# RS485NFlash.net
KiCad netlist of a schematic drawn in Altium Designer
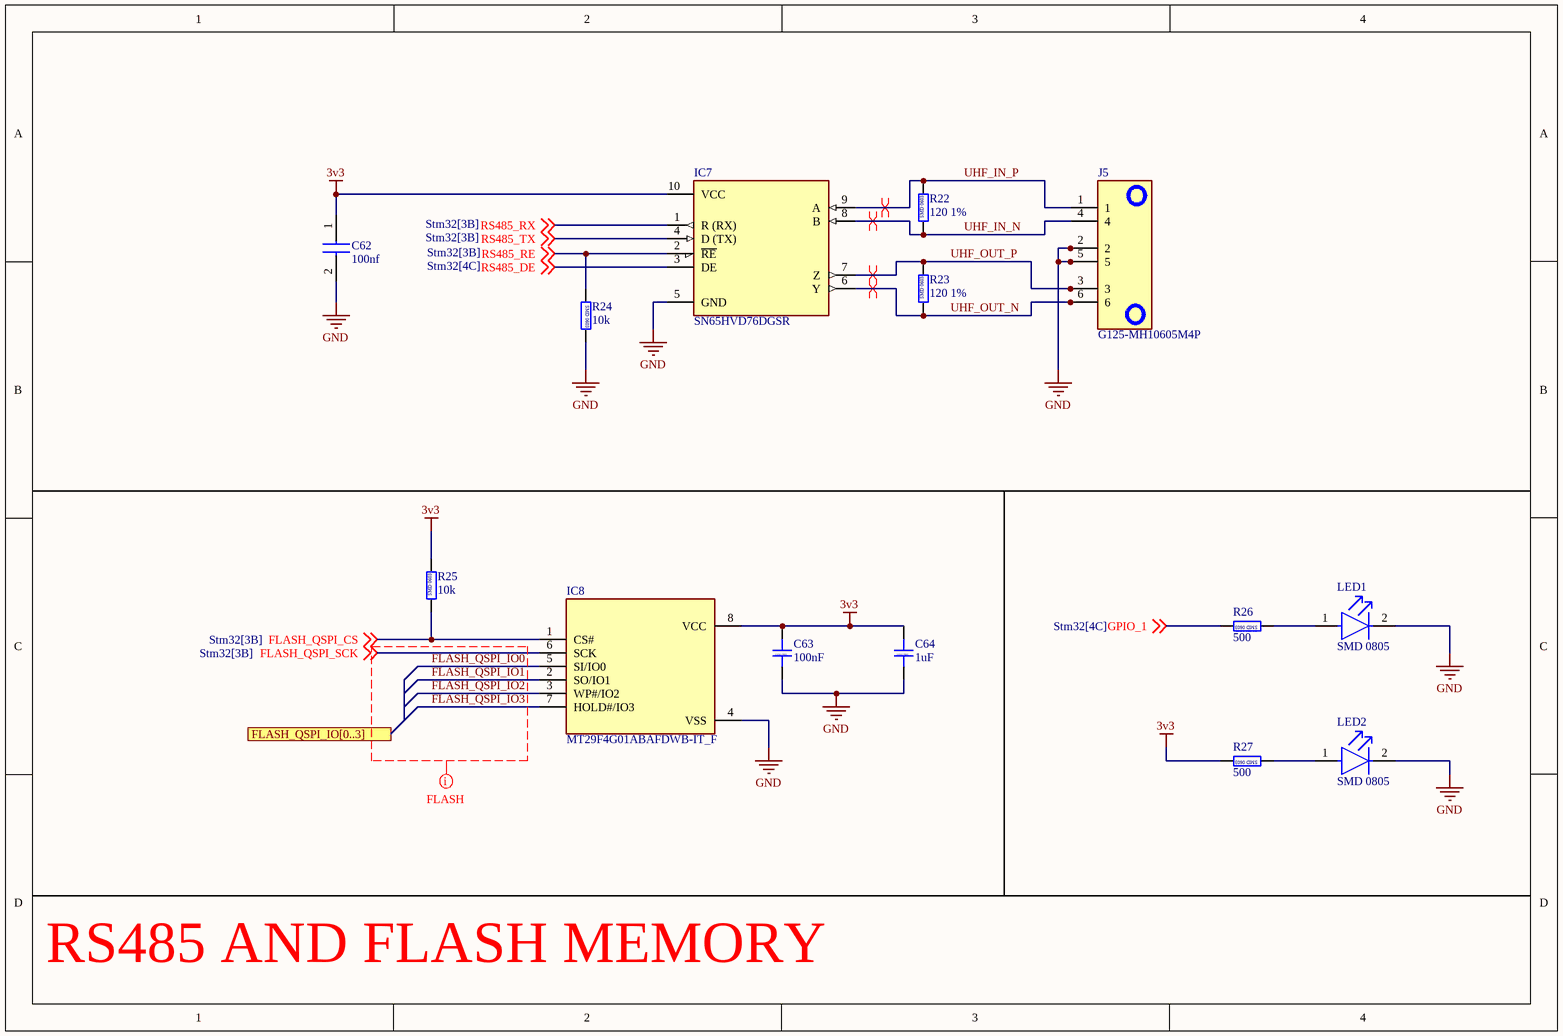
[diagram p0: RS485NFlash.SchDoc]

(export (version "E")
  (design (tool "Eeschema 10.0.6"))
  (components
    (comp (ref "C62")
      (value "100nf")
      (footprint "SamacSys:CAPC1608X87N")
      (description "Capacitor")
      (fields
        (field (name "MANUFACTURER_PART_NUMBER") "0603N470J500CT")
        (field (name "MOUSER PART NUMBER") "791-0603N470J500CT")
      )
      (libsource (lib "SamacSys") (part "0603N470J500CT"))
    )
    (comp (ref "C63")
      (value "100nF")
      (footprint "CAP_0603")
      (description "Capacitor SMD 0603 RATED")
      (libsource (lib "STeRG-Passives-Standard") (part "Capacitor-SMD-0603"))
    )
    (comp (ref "C64")
      (value "1uF")
      (footprint "CAP_0603")
      (description "Capacitor SMD 0603 RATED")
      (libsource (lib "STeRG-Passives-Standard") (part "Capacitor-SMD-0603"))
    )
    (comp (ref "IC7")
      (value "SN65HVD76DGSR")
      (footprint "SOP50P490X110-10N")
      (description "RS485 Full Duplex Transciever")
      (fields (field (name "MOUSER PART NUMBER") "595-SN65HVD76DGSR"))
      (libsource (lib "STeRG-ICs-Standard") (part "SN65HVD76DGSR"))
    )
    (comp (ref "IC8")
      (value "MT29F4G01ABAFDWB-IT_F")
      (footprint "SamacSys:SON127P800X600X65-8N")
      (description "Integrated Circuit")
      (fields
        (field (name "MANUFACTURER_PART_NUMBER") "MT29F4G01ABAFDWB-IT:F")
        (field (name "MOUSER PART NUMBER") "340-359563")
      )
      (libsource (lib "SamacSys") (part "MT29F4G01ABAFDWB-IT_F"))
    )
    (comp (ref "J5")
      (value "G125-MH10605M4P")
      (footprint "G125-MH10605M4P_1")
      (description "Connector")
      (fields (field (name "MOUSER PART NUMBER") "855-G125MH1065M4PM4P"))
      (libsource (lib "STeRG-Passives-Standard") (part "G125-MH10605M4P"))
    )
    (comp (ref "LED1")
      (value "SMD 0805")
      (footprint "FP-SM0805YCL-MFG")
      (description "LED YELLOW CLEAR 0805 SMD")
      (libsource (lib "Altium Content Vault") (part "ab1c01a81903e929fc6c44469aada92"))
    )
    (comp (ref "LED2")
      (value "SMD 0805")
      (footprint "FP-SM0805YCL-MFG")
      (description "LED YELLOW CLEAR 0805 SMD")
      (libsource (lib "Altium Content Vault") (part "ab1c01a81903e929fc6c44469aada92"))
    )
    (comp (ref "R22")
      (value "120 1%")
      (footprint "RES_0603")
      (description "Resistor SMD 0603 RATED")
      (libsource (lib "STeRG-Passives-Standard") (part "Resistor-SMD-0603"))
    )
    (comp (ref "R23")
      (value "120 1%")
      (footprint "RES_0603")
      (description "Resistor SMD 0603 RATED")
      (libsource (lib "STeRG-Passives-Standard") (part "Resistor-SMD-0603"))
    )
    (comp (ref "R24")
      (value "10k")
      (footprint "RES_0603")
      (description "Resistor SMD 0603 RATED")
      (libsource (lib "STeRG-Passives-Standard") (part "Resistor-SMD-0603"))
    )
    (comp (ref "R25")
      (value "10k")
      (footprint "RES_0603")
      (description "Resistor SMD 0603 RATED")
      (libsource (lib "STeRG-Passives-Standard") (part "Resistor-SMD-0603"))
    )
    (comp (ref "R26")
      (value "500")
      (footprint "RES_0603")
      (description "Resistor SMD 0603 RATED")
      (libsource (lib "STeRG-Passives-Standard") (part "Resistor-SMD-0603"))
    )
    (comp (ref "R27")
      (value "500")
      (footprint "RES_0603")
      (description "Resistor SMD 0603 RATED")
      (libsource (lib "STeRG-Passives-Standard") (part "Resistor-SMD-0603"))
    )
  )
  (nets
    (net (code "1") (name "/FLASH_QSPI_IO0") (class "Default")
      (node (ref "IC8") (pin "5") (pinfunction "SI/IO0_5") (pintype "passive"))
    )
    (net (code "2") (name "/FLASH_QSPI_IO1") (class "Default")
      (node (ref "IC8") (pin "2") (pinfunction "SO/IO1_2") (pintype "passive"))
    )
    (net (code "3") (name "/FLASH_QSPI_IO2") (class "Default")
      (node (ref "IC8") (pin "3") (pinfunction "WP#/IO2_3") (pintype "passive"))
    )
    (net (code "4") (name "/FLASH_QSPI_IO3") (class "Default")
      (node (ref "IC8") (pin "7") (pinfunction "HOLD#/IO3_7") (pintype "passive"))
    )
    (net (code "6") (name "/UHF_IN_N") (class "Default")
      (node (ref "IC7") (pin "8") (pinfunction "B_8") (pintype "input"))
      (node (ref "J5") (pin "4") (pinfunction "4_4") (pintype "passive"))
      (node (ref "R22") (pin "1") (pinfunction "1_1") (pintype "passive"))
    )
    (net (code "7") (name "/UHF_IN_P") (class "Default")
      (node (ref "IC7") (pin "9") (pinfunction "A_9") (pintype "input"))
      (node (ref "J5") (pin "1") (pinfunction "1_1") (pintype "passive"))
      (node (ref "R22") (pin "2") (pinfunction "2_2") (pintype "passive"))
    )
    (net (code "8") (name "/UHF_OUT_N") (class "Default")
      (node (ref "IC7") (pin "6") (pinfunction "Y_6") (pintype "output"))
      (node (ref "J5") (pin "6") (pinfunction "6_6") (pintype "passive"))
      (node (ref "R23") (pin "1") (pinfunction "1_1") (pintype "passive"))
    )
    (net (code "9") (name "/UHF_OUT_P") (class "Default")
      (node (ref "IC7") (pin "7") (pinfunction "Z_7") (pintype "output"))
      (node (ref "J5") (pin "3") (pinfunction "3_3") (pintype "passive"))
      (node (ref "R23") (pin "2") (pinfunction "2_2") (pintype "passive"))
    )
    (net (code "10") (name "3v3") (class "Default")
      (node (ref "C62") (pin "1") (pinfunction "1_1") (pintype "passive"))
      (node (ref "C63") (pin "2") (pinfunction "2_2") (pintype "passive"))
      (node (ref "C64") (pin "2") (pinfunction "2_2") (pintype "passive"))
      (node (ref "IC7") (pin "10") (pinfunction "VCC_10") (pintype "passive"))
      (node (ref "IC8") (pin "8") (pinfunction "VCC_8") (pintype "passive"))
      (node (ref "R25") (pin "2") (pinfunction "2_2") (pintype "passive"))
      (node (ref "R27") (pin "2") (pinfunction "2_2") (pintype "passive"))
    )
    (net (code "11") (name "FLASH_QSPI_CS") (class "Default")
      (node (ref "IC8") (pin "1") (pinfunction "CS#_1") (pintype "passive"))
      (node (ref "R25") (pin "1") (pinfunction "1_1") (pintype "passive"))
    )
    (net (code "12") (name "FLASH_QSPI_SCK") (class "Default")
      (node (ref "IC8") (pin "6") (pinfunction "SCK_6") (pintype "passive"))
    )
    (net (code "13") (name "GND") (class "Default")
      (node (ref "C62") (pin "2") (pinfunction "2_2") (pintype "passive"))
      (node (ref "C63") (pin "1") (pinfunction "1_1") (pintype "passive"))
      (node (ref "C64") (pin "1") (pinfunction "1_1") (pintype "passive"))
      (node (ref "IC7") (pin "5") (pinfunction "GND_5") (pintype "passive"))
      (node (ref "IC8") (pin "4") (pinfunction "VSS_4") (pintype "passive"))
      (node (ref "J5") (pin "2") (pinfunction "2_2") (pintype "passive"))
      (node (ref "J5") (pin "5") (pinfunction "5_5") (pintype "passive"))
      (node (ref "LED1") (pin "2") (pinfunction "C_2") (pintype "passive"))
      (node (ref "LED2") (pin "2") (pinfunction "C_2") (pintype "passive"))
      (node (ref "R24") (pin "2") (pinfunction "2_2") (pintype "passive"))
    )
    (net (code "14") (name "GPIO_1") (class "Default")
      (node (ref "R26") (pin "2") (pinfunction "2_2") (pintype "passive"))
    )
    (net (code "15") (name "Net-(LED1-A)") (class "Default")
      (node (ref "LED1") (pin "1") (pinfunction "A_1") (pintype "passive"))
      (node (ref "R26") (pin "1") (pinfunction "1_1") (pintype "passive"))
    )
    (net (code "16") (name "Net-(LED2-A)") (class "Default")
      (node (ref "LED2") (pin "1") (pinfunction "A_1") (pintype "passive"))
      (node (ref "R27") (pin "1") (pinfunction "1_1") (pintype "passive"))
    )
    (net (code "17") (name "RS485_DE") (class "Default")
      (node (ref "IC7") (pin "3") (pinfunction "DE_3") (pintype "passive"))
    )
    (net (code "18") (name "RS485_RE") (class "Default")
      (node (ref "IC7") (pin "2") (pinfunction "~{RE}_2") (pintype "passive"))
      (node (ref "R24") (pin "1") (pinfunction "1_1") (pintype "passive"))
    )
    (net (code "19") (name "RS485_RX") (class "Default")
      (node (ref "IC7") (pin "1") (pinfunction "R_(RX)_1") (pintype "output"))
    )
    (net (code "20") (name "RS485_TX") (class "Default")
      (node (ref "IC7") (pin "4") (pinfunction "D_(TX)_4") (pintype "input"))
    )
  )
)
